# master-board.net
KiCad netlist of a schematic drawn in EAGLE
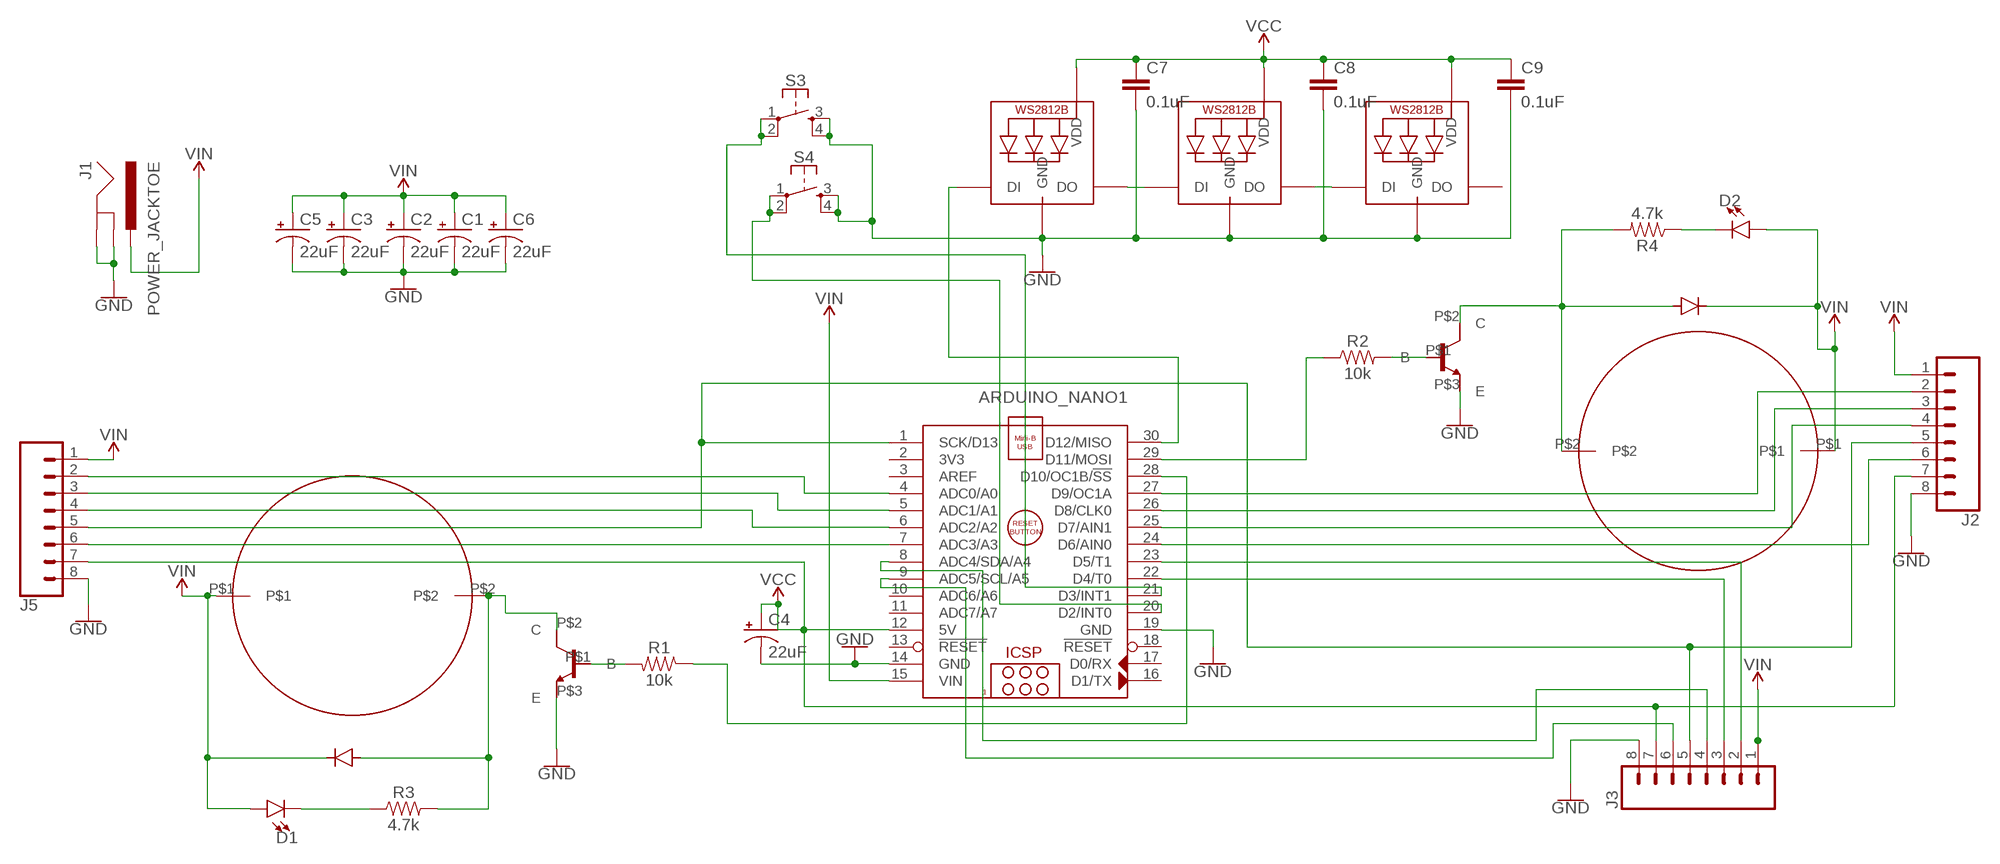
[diagram p0: schematic, sheet 1]

(export (version "E")
  (design (tool "Eeschema 10.0.6"))
  (components
    (comp (ref "ARDUINO_NANO1")
      (value "ARDUINO_NANO")
      (footprint "eagle-import:ARDUINO_NANO")
      (libsource (lib "eagle-import") (part "ARDUINO_NANO"))
    )
    (comp (ref "C1")
      (value "22uF")
      (footprint "eagle-import:PANASONIC_C")
      (libsource (lib "eagle-import") (part "22UF-POLAR-PANASONIC_C-35V-20%"))
    )
    (comp (ref "C2")
      (value "22uF")
      (footprint "eagle-import:PANASONIC_C")
      (libsource (lib "eagle-import") (part "22UF-POLAR-PANASONIC_C-35V-20%"))
    )
    (comp (ref "C3")
      (value "22uF")
      (footprint "eagle-import:PANASONIC_C")
      (libsource (lib "eagle-import") (part "22UF-POLAR-PANASONIC_C-35V-20%"))
    )
    (comp (ref "C4")
      (value "22uF")
      (footprint "eagle-import:PANASONIC_C")
      (libsource (lib "eagle-import") (part "22UF-POLAR-PANASONIC_C-35V-20%"))
    )
    (comp (ref "C5")
      (value "22uF")
      (footprint "eagle-import:PANASONIC_C")
      (libsource (lib "eagle-import") (part "22UF-POLAR-PANASONIC_C-35V-20%"))
    )
    (comp (ref "C6")
      (value "22uF")
      (footprint "eagle-import:PANASONIC_C")
      (libsource (lib "eagle-import") (part "22UF-POLAR-PANASONIC_C-35V-20%"))
    )
    (comp (ref "C7")
      (value "0.1uF")
      (footprint "eagle-import:0603")
      (libsource (lib "eagle-import") (part "0.1UF-0603-25V-(+80/-20%)"))
    )
    (comp (ref "C8")
      (value "0.1uF")
      (footprint "eagle-import:0603")
      (libsource (lib "eagle-import") (part "0.1UF-0603-25V-(+80/-20%)"))
    )
    (comp (ref "C9")
      (value "0.1uF")
      (footprint "eagle-import:0603")
      (libsource (lib "eagle-import") (part "0.1UF-0603-25V-(+80/-20%)"))
    )
    (comp (ref "D1")
      (value "LED0603")
      (footprint "eagle-import:LED-0603")
      (libsource (lib "eagle-import") (part "LED0603"))
    )
    (comp (ref "D2")
      (value "LED0603")
      (footprint "eagle-import:LED-0603")
      (libsource (lib "eagle-import") (part "LED0603"))
    )
    (comp (ref "J1")
      (value "POWER_JACKTOE")
      (footprint "eagle-import:POWER_JACK_SMD_OVERPASTE_TOE")
      (libsource (lib "eagle-import") (part "POWER_JACKTOE"))
    )
    (comp (ref "J2")
      (value "CONN_08\"")
      (footprint "eagle-import:1X08")
      (libsource (lib "eagle-import") (part "CONN_08{dblquote}"))
    )
    (comp (ref "J3")
      (value "CONN_08\"")
      (footprint "eagle-import:1X08")
      (libsource (lib "eagle-import") (part "CONN_08{dblquote}"))
    )
    (comp (ref "J5")
      (value "CONN_08\"")
      (footprint "eagle-import:1X08")
      (libsource (lib "eagle-import") (part "CONN_08{dblquote}"))
    )
    (comp (ref "LED1")
      (value "WS2812B5050")
      (footprint "eagle-import:WS2812B")
      (libsource (lib "eagle-import") (part "WS2812B5050"))
    )
    (comp (ref "LED2")
      (value "WS2812B5050")
      (footprint "eagle-import:WS2812B")
      (libsource (lib "eagle-import") (part "WS2812B5050"))
    )
    (comp (ref "LED3")
      (value "WS2812B5050")
      (footprint "eagle-import:WS2812B")
      (libsource (lib "eagle-import") (part "WS2812B5050"))
    )
    (comp (ref "R1")
      (value "10k")
      (footprint "eagle-import:0603")
      (libsource (lib "eagle-import") (part "10KOHM-0603-1/10W-1%"))
    )
    (comp (ref "R2")
      (value "10k")
      (footprint "eagle-import:0603")
      (libsource (lib "eagle-import") (part "10KOHM-0603-1/10W-1%"))
    )
    (comp (ref "R3")
      (value "4.7k")
      (footprint "eagle-import:0603")
      (libsource (lib "eagle-import") (part "4.7KOHM-0603-1/10W-1%"))
    )
    (comp (ref "R4")
      (value "4.7k")
      (footprint "eagle-import:0603")
      (libsource (lib "eagle-import") (part "4.7KOHM-0603-1/10W-1%"))
    )
    (comp (ref "S3")
      (value "MOMENTARY-SWITCH-SPST-2-SMD-4.6X2.8MM")
      (footprint "eagle-import:TACTILE_SWITCH_SMD_4.6X2.8MM")
      (libsource (lib "eagle-import") (part "MOMENTARY-SWITCH-SPST-2-SMD-4.6X2.8MM"))
    )
    (comp (ref "S4")
      (value "MOMENTARY-SWITCH-SPST-2-SMD-4.6X2.8MM")
      (footprint "eagle-import:TACTILE_SWITCH_SMD_4.6X2.8MM")
      (libsource (lib "eagle-import") (part "MOMENTARY-SWITCH-SPST-2-SMD-4.6X2.8MM"))
    )
    (comp (ref "U$1")
      (value "AIYIMA-PUMP-A5F083")
      (footprint "eagle-import:A5F083")
      (libsource (lib "eagle-import") (part "AIYIMA-PUMP-A5F083"))
    )
    (comp (ref "U$2")
      (value "AIYIMA-PUMP-A5F083")
      (footprint "eagle-import:A5F083")
      (libsource (lib "eagle-import") (part "AIYIMA-PUMP-A5F083"))
    )
    (comp (ref "U$3")
      (value "IN4148")
      (footprint "eagle-import:IN4148")
      (libsource (lib "eagle-import") (part "IN4148"))
    )
    (comp (ref "U$4")
      (value "IN4148")
      (footprint "eagle-import:IN4148")
      (libsource (lib "eagle-import") (part "IN4148"))
    )
    (comp (ref "U$5")
      (value "TIP120-TO220")
      (footprint "eagle-import:TO220")
      (libsource (lib "eagle-import") (part "TIP120-TO220"))
    )
    (comp (ref "U$6")
      (value "TIP120-TO220")
      (footprint "eagle-import:TO220")
      (libsource (lib "eagle-import") (part "TIP120-TO220"))
    )
  )
  (nets
    (net (code "1") (name "GND") (class "Default")
      (node (ref "ARDUINO_NANO1") (pin "14") (pinfunction "GND_14") (pintype "power_in"))
      (node (ref "ARDUINO_NANO1") (pin "19") (pinfunction "GND_19") (pintype "power_in"))
      (node (ref "C1") (pin "-") (pinfunction "-_-") (pintype "passive"))
      (node (ref "C2") (pin "-") (pinfunction "-_-") (pintype "passive"))
      (node (ref "C3") (pin "-") (pinfunction "-_-") (pintype "passive"))
      (node (ref "C4") (pin "-") (pinfunction "-_-") (pintype "passive"))
      (node (ref "C5") (pin "-") (pinfunction "-_-") (pintype "passive"))
      (node (ref "C6") (pin "-") (pinfunction "-_-") (pintype "passive"))
      (node (ref "C7") (pin "2") (pinfunction "2_2") (pintype "passive"))
      (node (ref "C8") (pin "2") (pinfunction "2_2") (pintype "passive"))
      (node (ref "C9") (pin "2") (pinfunction "2_2") (pintype "passive"))
      (node (ref "J1") (pin "GND") (pinfunction "GNDBREAK_GND") (pintype "bidirectional"))
      (node (ref "J1") (pin "P$4") (pinfunction "GND_P$4") (pintype "bidirectional"))
      (node (ref "J2") (pin "8") (pinfunction "8_8") (pintype "passive"))
      (node (ref "J3") (pin "8") (pinfunction "8_8") (pintype "passive"))
      (node (ref "J5") (pin "8") (pinfunction "8_8") (pintype "passive"))
      (node (ref "LED1") (pin "3-GND") (pinfunction "GND_3-GND") (pintype "power_in"))
      (node (ref "LED2") (pin "3-GND") (pinfunction "GND_3-GND") (pintype "power_in"))
      (node (ref "LED3") (pin "3-GND") (pinfunction "GND_3-GND") (pintype "power_in"))
      (node (ref "S3") (pin "3") (pinfunction "3_3") (pintype "passive"))
      (node (ref "S3") (pin "4") (pinfunction "4_4") (pintype "passive"))
      (node (ref "S4") (pin "3") (pinfunction "3_3") (pintype "passive"))
      (node (ref "S4") (pin "4") (pinfunction "4_4") (pintype "passive"))
      (node (ref "U$5") (pin "P$3") (pinfunction "E_P$3") (pintype "bidirectional"))
      (node (ref "U$6") (pin "P$3") (pinfunction "E_P$3") (pintype "bidirectional"))
    )
    (net (code "2") (name "Net-(ARDUINO_NANO1-ADC0{slash}A0)") (class "Default")
      (node (ref "ARDUINO_NANO1") (pin "4") (pinfunction "ADC0/A0_4") (pintype "bidirectional"))
      (node (ref "J5") (pin "2") (pinfunction "2_2") (pintype "passive"))
    )
    (net (code "3") (name "Net-(ARDUINO_NANO1-ADC1{slash}A1)") (class "Default")
      (node (ref "ARDUINO_NANO1") (pin "5") (pinfunction "ADC1/A1_5") (pintype "bidirectional"))
      (node (ref "J5") (pin "3") (pinfunction "3_3") (pintype "passive"))
    )
    (net (code "4") (name "Net-(ARDUINO_NANO1-ADC2{slash}A2)") (class "Default")
      (node (ref "ARDUINO_NANO1") (pin "6") (pinfunction "ADC2/A2_6") (pintype "bidirectional"))
      (node (ref "J5") (pin "4") (pinfunction "4_4") (pintype "passive"))
    )
    (net (code "5") (name "Net-(ARDUINO_NANO1-ADC3{slash}A3)") (class "Default")
      (node (ref "ARDUINO_NANO1") (pin "7") (pinfunction "ADC3/A3_7") (pintype "bidirectional"))
      (node (ref "J5") (pin "6") (pinfunction "6_6") (pintype "passive"))
    )
    (net (code "6") (name "Net-(ARDUINO_NANO1-ADC4{slash}SDA{slash}A4)") (class "Default")
      (node (ref "ARDUINO_NANO1") (pin "8") (pinfunction "ADC4/SDA/A4_8") (pintype "bidirectional"))
      (node (ref "J3") (pin "4") (pinfunction "4_4") (pintype "passive"))
    )
    (net (code "7") (name "Net-(ARDUINO_NANO1-ADC5{slash}SCL{slash}A5)") (class "Default")
      (node (ref "ARDUINO_NANO1") (pin "9") (pinfunction "ADC5/SCL/A5_9") (pintype "bidirectional"))
      (node (ref "J3") (pin "6") (pinfunction "6_6") (pintype "passive"))
    )
    (net (code "8") (name "Net-(ARDUINO_NANO1-D2{slash}INT0)") (class "Default")
      (node (ref "ARDUINO_NANO1") (pin "20") (pinfunction "D2/INT0_20") (pintype "bidirectional"))
      (node (ref "S4") (pin "1") (pinfunction "1_1") (pintype "passive"))
      (node (ref "S4") (pin "2") (pinfunction "2_2") (pintype "passive"))
    )
    (net (code "9") (name "Net-(ARDUINO_NANO1-D3{slash}INT1)") (class "Default")
      (node (ref "ARDUINO_NANO1") (pin "21") (pinfunction "D3/INT1_21") (pintype "bidirectional"))
      (node (ref "S3") (pin "1") (pinfunction "1_1") (pintype "passive"))
      (node (ref "S3") (pin "2") (pinfunction "2_2") (pintype "passive"))
    )
    (net (code "10") (name "Net-(ARDUINO_NANO1-D4{slash}T0)") (class "Default")
      (node (ref "ARDUINO_NANO1") (pin "22") (pinfunction "D4/T0_22") (pintype "bidirectional"))
      (node (ref "J3") (pin "3") (pinfunction "3_3") (pintype "passive"))
    )
    (net (code "11") (name "Net-(ARDUINO_NANO1-D5{slash}T1)") (class "Default")
      (node (ref "ARDUINO_NANO1") (pin "23") (pinfunction "D5/T1_23") (pintype "bidirectional"))
      (node (ref "J3") (pin "2") (pinfunction "2_2") (pintype "passive"))
    )
    (net (code "12") (name "Net-(ARDUINO_NANO1-D6{slash}AIN0)") (class "Default")
      (node (ref "ARDUINO_NANO1") (pin "24") (pinfunction "D6/AIN0_24") (pintype "bidirectional"))
      (node (ref "J2") (pin "6") (pinfunction "6_6") (pintype "passive"))
    )
    (net (code "13") (name "Net-(ARDUINO_NANO1-D7{slash}AIN1)") (class "Default")
      (node (ref "ARDUINO_NANO1") (pin "25") (pinfunction "D7/AIN1_25") (pintype "bidirectional"))
      (node (ref "J2") (pin "4") (pinfunction "4_4") (pintype "passive"))
    )
    (net (code "14") (name "Net-(ARDUINO_NANO1-D8{slash}CLK0)") (class "Default")
      (node (ref "ARDUINO_NANO1") (pin "26") (pinfunction "D8/CLK0_26") (pintype "bidirectional"))
      (node (ref "J2") (pin "3") (pinfunction "3_3") (pintype "passive"))
    )
    (net (code "15") (name "Net-(ARDUINO_NANO1-D9{slash}OC1A)") (class "Default")
      (node (ref "ARDUINO_NANO1") (pin "27") (pinfunction "D9/OC1A_27") (pintype "bidirectional"))
      (node (ref "J2") (pin "2") (pinfunction "2_2") (pintype "passive"))
    )
    (net (code "16") (name "Net-(ARDUINO_NANO1-D10{slash}OC1B{slash}~{SS})") (class "Default")
      (node (ref "ARDUINO_NANO1") (pin "28") (pinfunction "D10/OC1B/~{SS}_28") (pintype "bidirectional"))
      (node (ref "R1") (pin "1") (pinfunction "1_1") (pintype "passive"))
    )
    (net (code "17") (name "Net-(ARDUINO_NANO1-D11{slash}MOSI)") (class "Default")
      (node (ref "ARDUINO_NANO1") (pin "29") (pinfunction "D11/MOSI_29") (pintype "bidirectional"))
      (node (ref "R2") (pin "1") (pinfunction "1_1") (pintype "passive"))
    )
    (net (code "18") (name "Net-(ARDUINO_NANO1-D12{slash}MISO)") (class "Default")
      (node (ref "ARDUINO_NANO1") (pin "30") (pinfunction "D12/MISO_30") (pintype "bidirectional"))
      (node (ref "LED1") (pin "4-DIN") (pinfunction "DI_4-DIN") (pintype "input"))
    )
    (net (code "19") (name "Net-(ARDUINO_NANO1-SCK{slash}D13)") (class "Default")
      (node (ref "ARDUINO_NANO1") (pin "1") (pinfunction "SCK/D13_1") (pintype "bidirectional"))
      (node (ref "J2") (pin "5") (pinfunction "5_5") (pintype "passive"))
      (node (ref "J3") (pin "5") (pinfunction "5_5") (pintype "passive"))
      (node (ref "J5") (pin "5") (pinfunction "5_5") (pintype "passive"))
    )
    (net (code "20") (name "Net-(D1-PadC)") (class "Default")
      (node (ref "D1") (pin "C") (pinfunction "C_C") (pintype "passive"))
      (node (ref "R3") (pin "1") (pinfunction "1_1") (pintype "passive"))
    )
    (net (code "21") (name "Net-(D2-PadC)") (class "Default")
      (node (ref "D2") (pin "C") (pinfunction "C_C") (pintype "passive"))
      (node (ref "R4") (pin "1") (pinfunction "1_1") (pintype "passive"))
    )
    (net (code "22") (name "Net-(LED1-DO)") (class "Default")
      (node (ref "LED1") (pin "2-DOUT") (pinfunction "DO_2-DOUT") (pintype "output"))
      (node (ref "LED2") (pin "4-DIN") (pinfunction "DI_4-DIN") (pintype "input"))
    )
    (net (code "23") (name "Net-(LED2-DO)") (class "Default")
      (node (ref "LED2") (pin "2-DOUT") (pinfunction "DO_2-DOUT") (pintype "output"))
      (node (ref "LED3") (pin "4-DIN") (pinfunction "DI_4-DIN") (pintype "input"))
    )
    (net (code "24") (name "Net-(U$5-B)") (class "Default")
      (node (ref "R2") (pin "2") (pinfunction "2_2") (pintype "passive"))
      (node (ref "U$5") (pin "P$1") (pinfunction "B_P$1") (pintype "bidirectional"))
    )
    (net (code "25") (name "Net-(U$5-C)") (class "Default")
      (node (ref "R4") (pin "2") (pinfunction "2_2") (pintype "passive"))
      (node (ref "U$2") (pin "P$2") (pinfunction "P$2_P$2") (pintype "bidirectional"))
      (node (ref "U$4") (pin "P$2") (pinfunction "P$2_P$2") (pintype "bidirectional"))
      (node (ref "U$5") (pin "P$2") (pinfunction "C_P$2") (pintype "bidirectional"))
    )
    (net (code "26") (name "Net-(U$6-B)") (class "Default")
      (node (ref "R1") (pin "2") (pinfunction "2_2") (pintype "passive"))
      (node (ref "U$6") (pin "P$1") (pinfunction "B_P$1") (pintype "bidirectional"))
    )
    (net (code "27") (name "Net-(U$6-C)") (class "Default")
      (node (ref "R3") (pin "2") (pinfunction "2_2") (pintype "passive"))
      (node (ref "U$1") (pin "P$2") (pinfunction "P$2_P$2") (pintype "bidirectional"))
      (node (ref "U$3") (pin "P$2") (pinfunction "P$2_P$2") (pintype "bidirectional"))
      (node (ref "U$6") (pin "P$2") (pinfunction "C_P$2") (pintype "bidirectional"))
    )
    (net (code "28") (name "VCC") (class "Default")
      (node (ref "ARDUINO_NANO1") (pin "12") (pinfunction "5V_12") (pintype "power_in"))
      (node (ref "C4") (pin "+") (pinfunction "+_+") (pintype "passive"))
      (node (ref "C7") (pin "1") (pinfunction "1_1") (pintype "passive"))
      (node (ref "C8") (pin "1") (pinfunction "1_1") (pintype "passive"))
      (node (ref "C9") (pin "1") (pinfunction "1_1") (pintype "passive"))
      (node (ref "J2") (pin "7") (pinfunction "7_7") (pintype "passive"))
      (node (ref "J3") (pin "7") (pinfunction "7_7") (pintype "passive"))
      (node (ref "J5") (pin "7") (pinfunction "7_7") (pintype "passive"))
      (node (ref "LED1") (pin "1-VDD") (pinfunction "VDD_1-VDD") (pintype "power_in"))
      (node (ref "LED2") (pin "1-VDD") (pinfunction "VDD_1-VDD") (pintype "power_in"))
      (node (ref "LED3") (pin "1-VDD") (pinfunction "VDD_1-VDD") (pintype "power_in"))
    )
    (net (code "29") (name "VIN") (class "Default")
      (node (ref "ARDUINO_NANO1") (pin "15") (pinfunction "VIN_15") (pintype "power_in"))
      (node (ref "C1") (pin "+") (pinfunction "+_+") (pintype "passive"))
      (node (ref "C2") (pin "+") (pinfunction "+_+") (pintype "passive"))
      (node (ref "C3") (pin "+") (pinfunction "+_+") (pintype "passive"))
      (node (ref "C5") (pin "+") (pinfunction "+_+") (pintype "passive"))
      (node (ref "C6") (pin "+") (pinfunction "+_+") (pintype "passive"))
      (node (ref "D1") (pin "A") (pinfunction "A_A") (pintype "passive"))
      (node (ref "D2") (pin "A") (pinfunction "A_A") (pintype "passive"))
      (node (ref "J1") (pin "VIN0") (pinfunction "PWR_VIN0") (pintype "bidirectional"))
      (node (ref "J2") (pin "1") (pinfunction "1_1") (pintype "passive"))
      (node (ref "J3") (pin "1") (pinfunction "1_1") (pintype "passive"))
      (node (ref "J5") (pin "1") (pinfunction "1_1") (pintype "passive"))
      (node (ref "U$1") (pin "P$1") (pinfunction "P$1_P$1") (pintype "bidirectional"))
      (node (ref "U$2") (pin "P$1") (pinfunction "P$1_P$1") (pintype "bidirectional"))
      (node (ref "U$3") (pin "P$1") (pinfunction "P$1_P$1") (pintype "bidirectional"))
      (node (ref "U$4") (pin "P$1") (pinfunction "P$1_P$1") (pintype "bidirectional"))
    )
    (net (code "30") (name "unconnected-(ARDUINO_NANO1-3V3-Pad2)") (class "Default")
      (node (ref "ARDUINO_NANO1") (pin "2") (pinfunction "3V3_2") (pintype "output"))
    )
    (net (code "31") (name "unconnected-(ARDUINO_NANO1-ADC6{slash}A6-Pad10)") (class "Default")
      (node (ref "ARDUINO_NANO1") (pin "10") (pinfunction "ADC6/A6_10") (pintype "bidirectional"))
    )
    (net (code "32") (name "unconnected-(ARDUINO_NANO1-ADC7{slash}A7-Pad11)") (class "Default")
      (node (ref "ARDUINO_NANO1") (pin "11") (pinfunction "ADC7/A7_11") (pintype "bidirectional"))
    )
    (net (code "33") (name "unconnected-(ARDUINO_NANO1-AREF-Pad3)") (class "Default")
      (node (ref "ARDUINO_NANO1") (pin "3") (pinfunction "AREF_3") (pintype "input"))
    )
    (net (code "34") (name "unconnected-(ARDUINO_NANO1-D0{slash}RX-Pad17)") (class "Default")
      (node (ref "ARDUINO_NANO1") (pin "17") (pinfunction "D0/RX_17") (pintype "bidirectional"))
    )
    (net (code "35") (name "unconnected-(ARDUINO_NANO1-D1{slash}TX-Pad16)") (class "Default")
      (node (ref "ARDUINO_NANO1") (pin "16") (pinfunction "D1/TX_16") (pintype "bidirectional"))
    )
    (net (code "36") (name "unconnected-(ARDUINO_NANO1-~{RESET}-Pad13)") (class "Default")
      (node (ref "ARDUINO_NANO1") (pin "13") (pinfunction "~{RESET}_13") (pintype "input"))
    )
    (net (code "37") (name "unconnected-(ARDUINO_NANO1-~{RESET}-Pad18)") (class "Default")
      (node (ref "ARDUINO_NANO1") (pin "18") (pinfunction "~{RESET}_18") (pintype "input"))
    )
    (net (code "38") (name "unconnected-(LED3-DO-Pad2-DOUT)") (class "Default")
      (node (ref "LED3") (pin "2-DOUT") (pinfunction "DO_2-DOUT") (pintype "output"))
    )
  )
)
